# PowerCore.net
KiCad netlist of a schematic drawn in Altium Designer
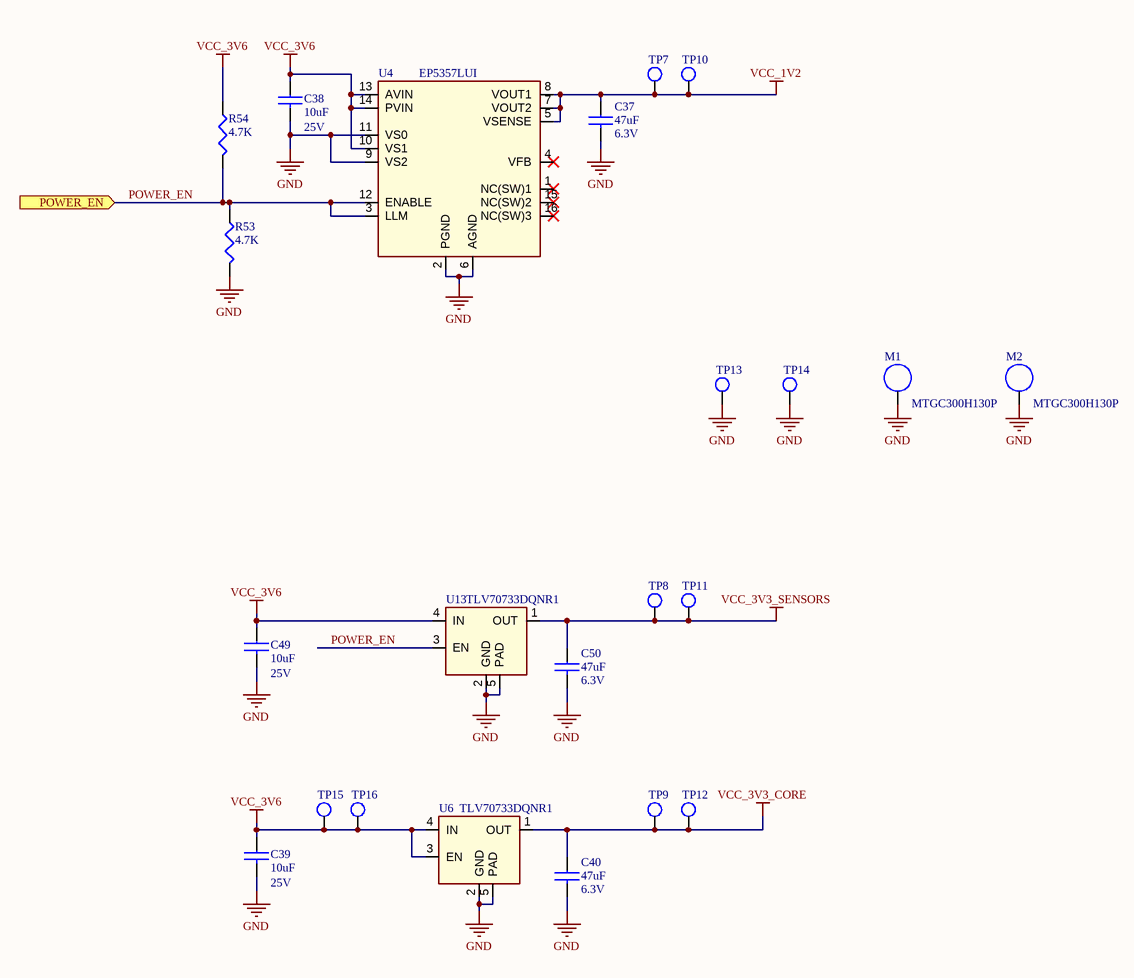
[diagram p0: PowerCore.SchDoc]

(export (version "E")
  (design (tool "Eeschema 10.0.6"))
  (components
    (comp (ref "C37")
      (value "47uF")
      (footprint "0805-ipcsm_145")
      (description "CAP CER 47UF 6.3V X5R 0805")
      (fields (field (name "VOLTAGE") "6.3V") (field (name "MFG") "Murata"))
      (libsource (lib "SynapseLibrary") (part "CAP"))
    )
    (comp (ref "C38")
      (value "10uF")
      (footprint "0603-ipcsm_90")
      (description "CAP CER 10UF 25V 20% X5R 0603")
      (fields
        (field (name "VOLTAGE") "25V")
        (field (name "MFG") "Samsung Electro-Mechanics America, Inc")
        (field (name "TOLERANCE") "20%")
      )
      (libsource (lib "SynapseLibrary") (part "CAP"))
    )
    (comp (ref "C39")
      (value "10uF")
      (footprint "0603-ipcsm_90")
      (description "CAP CER 10UF 25V 20% X5R 0603")
      (fields
        (field (name "VOLTAGE") "25V")
        (field (name "MFG") "Samsung Electro-Mechanics America, Inc")
        (field (name "TOLERANCE") "20%")
      )
      (libsource (lib "SynapseLibrary") (part "CAP"))
    )
    (comp (ref "C40")
      (value "47uF")
      (footprint "0805-ipcsm_145")
      (description "CAP CER 47UF 6.3V X5R 0805")
      (fields (field (name "VOLTAGE") "6.3V") (field (name "MFG") "Murata"))
      (libsource (lib "SynapseLibrary") (part "CAP"))
    )
    (comp (ref "C49")
      (value "10uF")
      (footprint "0603-ipcsm_90")
      (description "CAP CER 10UF 25V 20% X5R 0603")
      (fields
        (field (name "VOLTAGE") "25V")
        (field (name "MFG") "Samsung Electro-Mechanics America, Inc")
        (field (name "TOLERANCE") "20%")
      )
      (libsource (lib "SynapseLibrary") (part "CAP"))
    )
    (comp (ref "C50")
      (value "47uF")
      (footprint "0805-ipcsm_145")
      (description "CAP CER 47UF 6.3V X5R 0805")
      (fields (field (name "VOLTAGE") "6.3V") (field (name "MFG") "Murata"))
      (libsource (lib "SynapseLibrary") (part "CAP"))
    )
    (comp (ref "M1")
      (value "MTGC300H130P")
      (footprint "MTGC300H130P")
      (description "MTG, 3.00 mm Pad, 1.30 mm throughhole, PLATED")
      (libsource (lib "SynapseLibrary") (part "MTG"))
    )
    (comp (ref "M2")
      (value "MTGC300H130P")
      (footprint "MTGC300H130P")
      (description "MTG, 3.00 mm Pad, 1.30 mm throughhole, PLATED")
      (libsource (lib "SynapseLibrary") (part "MTG"))
    )
    (comp (ref "R53")
      (value "4.7K")
      (footprint "0201-IPCsm_26")
      (description "RES 4.70K OHM 1/20W 1% 0201 SMD")
      (fields (field (name "TOLERANCE") "1.00%") (field (name "MFG") "PANASONIC"))
      (libsource (lib "SynapseLibrary") (part "RES"))
    )
    (comp (ref "R54")
      (value "4.7K")
      (footprint "0201-IPCsm_26")
      (description "RES 4.70K OHM 1/20W 1% 0201 SMD")
      (fields (field (name "TOLERANCE") "1.00%") (field (name "MFG") "PANASONIC"))
      (libsource (lib "SynapseLibrary") (part "RES"))
    )
    (comp (ref "TP7")
      (value "tp-1mm")
      (footprint "TP-S100_SMT")
      (description "TESTPOINT, 1MM SMD, Square pad, Round SM opening")
      (fields (field (name "MFG") "NA"))
      (libsource (lib "SynapseLibrary") (part "tp_smt"))
    )
    (comp (ref "TP8")
      (value "tp-1mm")
      (footprint "TP-S100_SMT")
      (description "TESTPOINT, 1MM SMD, Square pad, Round SM opening")
      (fields (field (name "MFG") "NA"))
      (libsource (lib "SynapseLibrary") (part "tp_smt"))
    )
    (comp (ref "TP9")
      (value "tp-1mm")
      (footprint "TP-S100_SMT")
      (description "TESTPOINT, 1MM SMD, Square pad, Round SM opening")
      (fields (field (name "MFG") "NA"))
      (libsource (lib "SynapseLibrary") (part "tp_smt"))
    )
    (comp (ref "TP10")
      (value "tp-1mm")
      (footprint "TP-S100_SMT")
      (description "TESTPOINT, 1MM SMD, Square pad, Round SM opening")
      (fields (field (name "MFG") "NA"))
      (libsource (lib "SynapseLibrary") (part "tp_smt"))
    )
    (comp (ref "TP11")
      (value "tp-1mm")
      (footprint "TP-S100_SMT")
      (description "TESTPOINT, 1MM SMD, Square pad, Round SM opening")
      (fields (field (name "MFG") "NA"))
      (libsource (lib "SynapseLibrary") (part "tp_smt"))
    )
    (comp (ref "TP12")
      (value "tp-1mm")
      (footprint "TP-S100_SMT")
      (description "TESTPOINT, 1MM SMD, Square pad, Round SM opening")
      (fields (field (name "MFG") "NA"))
      (libsource (lib "SynapseLibrary") (part "tp_smt"))
    )
    (comp (ref "TP13")
      (value "tp-1mm")
      (footprint "TP-S100_SMT")
      (description "TESTPOINT, 1MM SMD, Square pad, Round SM opening")
      (fields (field (name "MFG") "NA"))
      (libsource (lib "SynapseLibrary") (part "tp_smt"))
    )
    (comp (ref "TP14")
      (value "tp-1mm")
      (footprint "TP-S100_SMT")
      (description "TESTPOINT, 1MM SMD, Square pad, Round SM opening")
      (fields (field (name "MFG") "NA"))
      (libsource (lib "SynapseLibrary") (part "tp_smt"))
    )
    (comp (ref "TP15")
      (value "tp-1mm")
      (footprint "TP-S100_SMT")
      (description "TESTPOINT, 1MM SMD, Square pad, Round SM opening")
      (fields (field (name "MFG") "NA"))
      (libsource (lib "SynapseLibrary") (part "tp_smt"))
    )
    (comp (ref "TP16")
      (value "tp-1mm")
      (footprint "TP-S100_SMT")
      (description "TESTPOINT, 1MM SMD, Square pad, Round SM opening")
      (fields (field (name "MFG") "NA"))
      (libsource (lib "SynapseLibrary") (part "tp_smt"))
    )
    (comp (ref "U4")
      (value "EP5357LUI")
      (footprint "qfn16_ep5357lui")
      (description "DC/DC CONVERTER 0.6-5.2V 3W")
      (fields (field (name "MFG") "Altera") (field (name "VOLTAGE") "2.4V~5.5V"))
      (libsource (lib "SynapseLibrary") (part "EP5357LUI"))
    )
    (comp (ref "U6")
      (value "TLV70733DQNR1")
      (footprint "son4_tlv707dqn")
      (description "IC REG LDO 3.3V 0.2A 4X2SON")
      (fields (field (name "MFG") "TI") (field (name "VOLTAGE") "2V~5.5V"))
      (libsource (lib "SynapseLibrary") (part "TLV707XX"))
    )
    (comp (ref "U13")
      (value "TLV70733DQNR1")
      (footprint "son4_tlv707dqn")
      (description "IC REG LDO 3.3V 0.2A 4X2SON")
      (fields (field (name "MFG") "TI") (field (name "VOLTAGE") "2V~5.5V"))
      (libsource (lib "SynapseLibrary") (part "TLV707XX"))
    )
  )
  (nets
    (net (code "1") (name "/POWER_EN") (class "Default")
      (node (ref "R53") (pin "1") (pinfunction "1_1") (pintype "passive"))
      (node (ref "R54") (pin "2") (pinfunction "2_2") (pintype "passive"))
      (node (ref "U13") (pin "3") (pinfunction "EN_3") (pintype "passive"))
      (node (ref "U4") (pin "12") (pinfunction "ENABLE_12") (pintype "passive"))
      (node (ref "U4") (pin "3") (pinfunction "LLM_3") (pintype "passive"))
    )
    (net (code "2") (name "GND") (class "Default")
      (node (ref "C37") (pin "2") (pinfunction "2_2") (pintype "passive"))
      (node (ref "C38") (pin "2") (pinfunction "2_2") (pintype "passive"))
      (node (ref "C39") (pin "2") (pinfunction "2_2") (pintype "passive"))
      (node (ref "C40") (pin "2") (pinfunction "2_2") (pintype "passive"))
      (node (ref "C49") (pin "2") (pinfunction "2_2") (pintype "passive"))
      (node (ref "C50") (pin "2") (pinfunction "2_2") (pintype "passive"))
      (node (ref "M1") (pin "1") (pinfunction "1_1") (pintype "passive"))
      (node (ref "M2") (pin "1") (pinfunction "1_1") (pintype "passive"))
      (node (ref "R53") (pin "2") (pinfunction "2_2") (pintype "passive"))
      (node (ref "TP13") (pin "1") (pinfunction "TP_1") (pintype "passive"))
      (node (ref "TP14") (pin "1") (pinfunction "TP_1") (pintype "passive"))
      (node (ref "U13") (pin "2") (pinfunction "GND_2") (pintype "passive"))
      (node (ref "U13") (pin "5") (pinfunction "PAD_5") (pintype "passive"))
      (node (ref "U4") (pin "11") (pinfunction "VS0_11") (pintype "passive"))
      (node (ref "U4") (pin "2") (pinfunction "PGND_2") (pintype "passive"))
      (node (ref "U4") (pin "6") (pinfunction "AGND_6") (pintype "passive"))
      (node (ref "U4") (pin "9") (pinfunction "VS2_9") (pintype "passive"))
      (node (ref "U6") (pin "2") (pinfunction "GND_2") (pintype "passive"))
      (node (ref "U6") (pin "5") (pinfunction "PAD_5") (pintype "passive"))
    )
    (net (code "3") (name "VCC_1V2") (class "Default")
      (node (ref "C37") (pin "1") (pinfunction "1_1") (pintype "passive"))
      (node (ref "TP10") (pin "1") (pinfunction "TP_1") (pintype "passive"))
      (node (ref "TP7") (pin "1") (pinfunction "TP_1") (pintype "passive"))
      (node (ref "U4") (pin "5") (pinfunction "VSENSE_5") (pintype "passive"))
      (node (ref "U4") (pin "7") (pinfunction "VOUT2_7") (pintype "passive"))
      (node (ref "U4") (pin "8") (pinfunction "VOUT1_8") (pintype "passive"))
    )
    (net (code "4") (name "VCC_3V3_CORE") (class "Default")
      (node (ref "C40") (pin "1") (pinfunction "1_1") (pintype "passive"))
      (node (ref "TP12") (pin "1") (pinfunction "TP_1") (pintype "passive"))
      (node (ref "TP9") (pin "1") (pinfunction "TP_1") (pintype "passive"))
      (node (ref "U6") (pin "1") (pinfunction "OUT_1") (pintype "passive"))
    )
    (net (code "5") (name "VCC_3V3_SENSORS") (class "Default")
      (node (ref "C50") (pin "1") (pinfunction "1_1") (pintype "passive"))
      (node (ref "TP11") (pin "1") (pinfunction "TP_1") (pintype "passive"))
      (node (ref "TP8") (pin "1") (pinfunction "TP_1") (pintype "passive"))
      (node (ref "U13") (pin "1") (pinfunction "OUT_1") (pintype "passive"))
    )
    (net (code "6") (name "VCC_3V6") (class "Default")
      (node (ref "C38") (pin "1") (pinfunction "1_1") (pintype "passive"))
      (node (ref "C39") (pin "1") (pinfunction "1_1") (pintype "passive"))
      (node (ref "C49") (pin "1") (pinfunction "1_1") (pintype "passive"))
      (node (ref "R54") (pin "1") (pinfunction "1_1") (pintype "passive"))
      (node (ref "TP15") (pin "1") (pinfunction "TP_1") (pintype "passive"))
      (node (ref "TP16") (pin "1") (pinfunction "TP_1") (pintype "passive"))
      (node (ref "U13") (pin "4") (pinfunction "IN_4") (pintype "passive"))
      (node (ref "U4") (pin "10") (pinfunction "VS1_10") (pintype "passive"))
      (node (ref "U4") (pin "13") (pinfunction "AVIN_13") (pintype "passive"))
      (node (ref "U4") (pin "14") (pinfunction "PVIN_14") (pintype "passive"))
      (node (ref "U6") (pin "3") (pinfunction "EN_3") (pintype "passive"))
      (node (ref "U6") (pin "4") (pinfunction "IN_4") (pintype "passive"))
    )
    (net (code "7") (name "unconnected-(U4-NC(SW)1-Pad1)") (class "Default")
      (node (ref "U4") (pin "1") (pinfunction "NC(SW)1_1") (pintype "passive+no_connect"))
    )
    (net (code "8") (name "unconnected-(U4-NC(SW)2-Pad15)") (class "Default")
      (node (ref "U4") (pin "15") (pinfunction "NC(SW)2_15") (pintype "passive+no_connect"))
    )
    (net (code "9") (name "unconnected-(U4-NC(SW)3-Pad16)") (class "Default")
      (node (ref "U4") (pin "16") (pinfunction "NC(SW)3_16") (pintype "passive+no_connect"))
    )
    (net (code "10") (name "unconnected-(U4-VFB-Pad4)") (class "Default")
      (node (ref "U4") (pin "4") (pinfunction "VFB_4") (pintype "passive+no_connect"))
    )
  )
)
